# smol32src.net
KiCad netlist of a schematic drawn in EasyEDA Pro
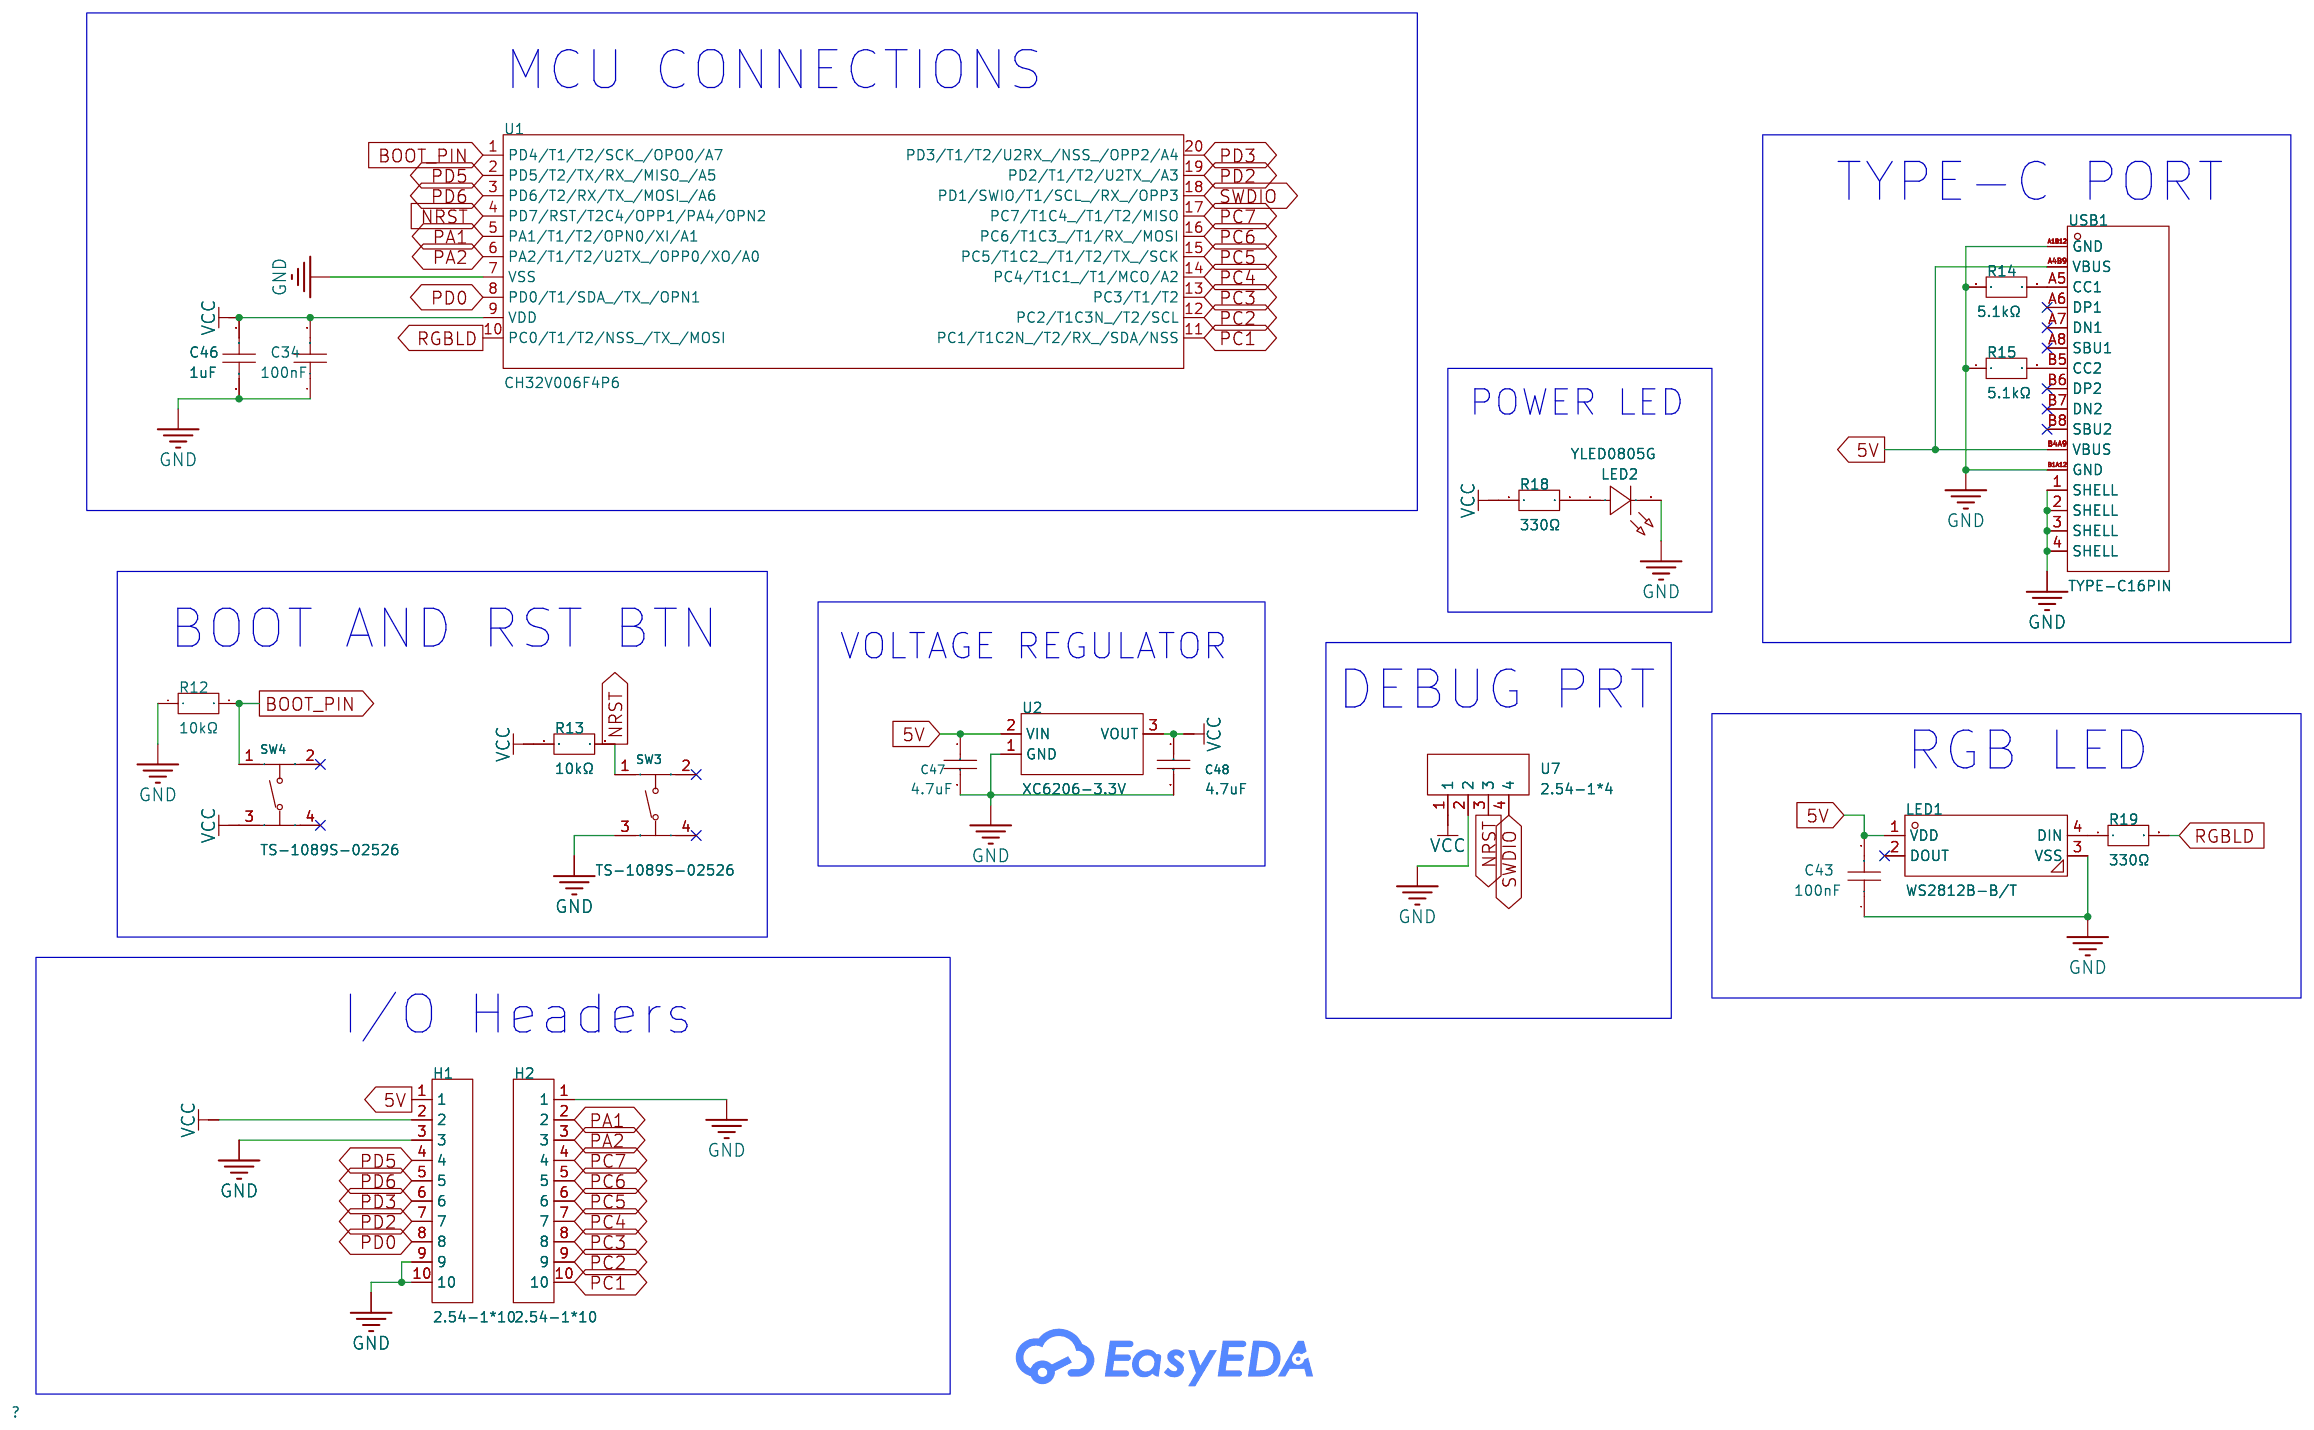
[diagram p0: schematic sheet]

(export (version "E")
  (design (tool "Eeschema 10.0.6"))
  (components
    (comp (ref "C34")
      (value "100nF")
      (footprint "easyedapro:C0603")
      (description "Capacitance:100nF Tolerance:±10% Tolerance:±10% Voltage Rating:50V Temperature Coefficient:X7R")
      (fields
        (field (name "Manufacturer Part") "FCC0603B104K500CT")
        (field (name "Manufacturer") "FOJAN(富捷)")
      )
      (libsource (lib "easyedapro") (part "FCC0603B104K500CT"))
    )
    (comp (ref "C43")
      (value "100nF")
      (footprint "easyedapro:C0603")
      (description "Capacitance:100nF Tolerance:±10% Tolerance:±10% Voltage Rating:50V Temperature Coefficient:X7R")
      (fields
        (field (name "Manufacturer Part") "FCC0603B104K500CT")
        (field (name "Manufacturer") "FOJAN(富捷)")
      )
      (libsource (lib "easyedapro") (part "FCC0603B104K500CT"))
    )
    (comp (ref "C46")
      (value "1uF")
      (footprint "easyedapro:C0603")
      (description "Capacitance:1uF Tolerance:±10% Tolerance:±10% Voltage Rating:50V Temperature Coefficient:X5R")
      (fields
        (field (name "Manufacturer Part") "CGA0603X5R105K500JT")
        (field (name "Manufacturer") "HRE(芯声)")
      )
      (libsource (lib "easyedapro") (part "CGA0603X5R105K500JT"))
    )
    (comp (ref "C47")
      (value "4.7uF")
      (footprint "easyedapro:C0603")
      (description "Capacitance:4.7uF Tolerance:±10% Tolerance:±10% Voltage Rating:10V Temperature Coefficient:X5R")
      (fields
        (field (name "Manufacturer Part") "CL10A475KP8NNNC")
        (field (name "Manufacturer") "SAMSUNG(三星)")
      )
      (libsource (lib "easyedapro") (part "CL10A475KP8NNNC"))
    )
    (comp (ref "C48")
      (value "4.7uF")
      (footprint "easyedapro:C0603")
      (description "Capacitance:4.7uF Tolerance:±10% Tolerance:±10% Voltage Rating:10V Temperature Coefficient:X5R")
      (fields
        (field (name "Manufacturer Part") "CL10A475KP8NNNC")
        (field (name "Manufacturer") "SAMSUNG(三星)")
      )
      (libsource (lib "easyedapro") (part "CL10A475KP8NNNC"))
    )
    (comp (ref "H1")
      (value "2.54-1*10")
      (footprint "easyedapro:HDR-TH_10P-P2.54-V-M")
      (fields (field (name "Manufacturer") "ZHOURI(洲日)"))
      (libsource (lib "easyedapro") (part "2.54-1*10"))
    )
    (comp (ref "H2")
      (value "2.54-1*10")
      (footprint "easyedapro:HDR-TH_10P-P2.54-V-M")
      (fields (field (name "Manufacturer") "ZHOURI(洲日)"))
      (libsource (lib "easyedapro") (part "2.54-1*10"))
    )
    (comp (ref "LED1")
      (value "WS2812B-B/T")
      (footprint "easyedapro:LED-SMD_4P-L5.0-W5.0-TL_WS2812B-B")
      (fields (field (name "Manufacturer") "worldsemi"))
      (libsource (lib "easyedapro") (part "WS2812B-B/W"))
    )
    (comp (ref "LED2")
      (value "YLED0805G")
      (footprint "easyedapro:LED0805-FD-GREEN")
      (fields (field (name "Manufacturer") "YONGYUTAI(永裕泰)"))
      (libsource (lib "easyedapro") (part "YLED0805G"))
    )
    (comp (ref "R12")
      (value "10kΩ")
      (footprint "easyedapro:R0603")
      (fields (field (name "Manufacturer Part") "FRC0603J103 TS") (field (name "Manufacturer") "FOJAN(富捷)"))
      (libsource (lib "easyedapro") (part "FRC0603J103TS"))
    )
    (comp (ref "R13")
      (value "10kΩ")
      (footprint "easyedapro:R0603")
      (fields (field (name "Manufacturer Part") "FRC0603J103 TS") (field (name "Manufacturer") "FOJAN(富捷)"))
      (libsource (lib "easyedapro") (part "FRC0603J103TS"))
    )
    (comp (ref "R14")
      (value "5.1kΩ")
      (footprint "easyedapro:R0603")
      (fields (field (name "Manufacturer Part") "FRC0603F5101TS") (field (name "Manufacturer") "FOJAN(富捷)"))
      (libsource (lib "easyedapro") (part "FRC0603F5101TS"))
    )
    (comp (ref "R15")
      (value "5.1kΩ")
      (footprint "easyedapro:R0603")
      (fields (field (name "Manufacturer Part") "FRC0603F5101TS") (field (name "Manufacturer") "FOJAN(富捷)"))
      (libsource (lib "easyedapro") (part "FRC0603F5101TS"))
    )
    (comp (ref "R18")
      (value "330Ω")
      (footprint "easyedapro:R0603")
      (fields (field (name "Manufacturer Part") "FRC0603J331 TS") (field (name "Manufacturer") "FOJAN(富捷)"))
      (libsource (lib "easyedapro") (part "FRC0603J331 TS"))
    )
    (comp (ref "R19")
      (value "330Ω")
      (footprint "easyedapro:R0603")
      (fields (field (name "Manufacturer Part") "FRC0603J331 TS") (field (name "Manufacturer") "FOJAN(富捷)"))
      (libsource (lib "easyedapro") (part "FRC0603J331 TS"))
    )
    (comp (ref "SW3")
      (value "TS-1089S-02526")
      (footprint "easyedapro:SW-SMD_4P-L4.2-W3.3-P2.15-LS5.1")
      (fields (field (name "Manufacturer") "XUNPU(讯普)"))
      (libsource (lib "easyedapro") (part "TS-1089S-02526"))
    )
    (comp (ref "SW4")
      (value "TS-1089S-02526")
      (footprint "easyedapro:SW-SMD_4P-L4.2-W3.3-P2.15-LS5.1")
      (fields (field (name "Manufacturer") "XUNPU(讯普)"))
      (libsource (lib "easyedapro") (part "TS-1089S-02526"))
    )
    (comp (ref "U1")
      (value "CH32V006F4P6")
      (footprint "easyedapro:TSSOP-20_L6.5-W4.4-P0.65-LS6.4-BL")
      (fields (field (name "Manufacturer") "WCH(南京沁恒)"))
      (libsource (lib "easyedapro") (part "CH32V006F8P6_C52753342"))
    )
    (comp (ref "U2")
      (value "XC6206-3.3V")
      (footprint "easyedapro:SOT-89-3_L4.3-W2.3-P1.50-LS4.3-BR")
      (description "Features:Short Circuit Protection；Over Current Protection")
      (fields (field (name "Manufacturer") "YONGYUTAI(永裕泰)"))
      (libsource (lib "easyedapro") (part "XC6206-3.3V_C7603199"))
    )
    (comp (ref "U7")
      (value "2.54-1*4")
      (footprint "easyedapro:HDR-TH_4P-P2.54-V-M-1")
      (fields (field (name "Manufacturer") "ZHOURI(洲日)"))
      (libsource (lib "easyedapro") (part "2.54-1*4"))
    )
    (comp (ref "USB1")
      (value "TYPE-C16PIN")
      (footprint "easyedapro:USB-C-SMD_TYPE-C16PIN")
      (fields (field (name "Manufacturer") "SHOU HAN(首韩)"))
      (libsource (lib "easyedapro") (part "TYPE-C16PIN"))
    )
  )
  (nets
    (net (code "1") (name "5V") (class "Default")
      (node (ref "C43") (pin "2") (pinfunction "2_2") (pintype "unspecified"))
      (node (ref "C47") (pin "1") (pinfunction "1_1") (pintype "input"))
      (node (ref "H1") (pin "1") (pinfunction "1_1") (pintype "unspecified"))
      (node (ref "LED1") (pin "1") (pinfunction "VDD_1") (pintype "unspecified"))
      (node (ref "U2") (pin "2") (pinfunction "VIN_2") (pintype "unspecified"))
      (node (ref "USB1") (pin "A4B9") (pinfunction "VBUS_A4B9") (pintype "unspecified"))
      (node (ref "USB1") (pin "B4A9") (pinfunction "VBUS_B4A9") (pintype "unspecified"))
    )
    (net (code "2") (name "BOOT_PIN") (class "Default")
      (node (ref "R12") (pin "2") (pinfunction "2_2") (pintype "unspecified"))
      (node (ref "SW4") (pin "1") (pinfunction "1_1") (pintype "input"))
      (node (ref "U1") (pin "1") (pinfunction "PD4/T1/T2/SCK_/OPO0/A7_1") (pintype "unspecified"))
    )
    (net (code "3") (name "GND") (class "Default")
      (node (ref "C34") (pin "1") (pinfunction "1_1") (pintype "unspecified"))
      (node (ref "C43") (pin "1") (pinfunction "1_1") (pintype "unspecified"))
      (node (ref "C46") (pin "2") (pinfunction "2_2") (pintype "unspecified"))
      (node (ref "C47") (pin "2") (pinfunction "2_2") (pintype "input"))
      (node (ref "C48") (pin "2") (pinfunction "2_2") (pintype "input"))
      (node (ref "H1") (pin "10") (pinfunction "10_10") (pintype "unspecified"))
      (node (ref "H1") (pin "3") (pinfunction "3_3") (pintype "unspecified"))
      (node (ref "H1") (pin "9") (pinfunction "9_9") (pintype "unspecified"))
      (node (ref "H2") (pin "1") (pinfunction "1_1") (pintype "unspecified"))
      (node (ref "LED1") (pin "3") (pinfunction "VSS_3") (pintype "unspecified"))
      (node (ref "LED2") (pin "2") (pinfunction "K_2") (pintype "unspecified"))
      (node (ref "R12") (pin "1") (pinfunction "1_1") (pintype "unspecified"))
      (node (ref "R14") (pin "1") (pinfunction "1_1") (pintype "unspecified"))
      (node (ref "R15") (pin "1") (pinfunction "1_1") (pintype "unspecified"))
      (node (ref "SW3") (pin "3") (pinfunction "3_3") (pintype "input"))
      (node (ref "U1") (pin "7") (pinfunction "VSS_7") (pintype "unspecified"))
      (node (ref "U2") (pin "1") (pinfunction "GND_1") (pintype "unspecified"))
      (node (ref "U7") (pin "2") (pinfunction "2_2") (pintype "unspecified"))
      (node (ref "USB1") (pin "1") (pinfunction "SHELL_1") (pintype "unspecified"))
      (node (ref "USB1") (pin "2") (pinfunction "SHELL_2") (pintype "unspecified"))
      (node (ref "USB1") (pin "3") (pinfunction "SHELL_3") (pintype "unspecified"))
      (node (ref "USB1") (pin "4") (pinfunction "SHELL_4") (pintype "unspecified"))
      (node (ref "USB1") (pin "A1B12") (pinfunction "GND_A1B12") (pintype "unspecified"))
      (node (ref "USB1") (pin "B1A12") (pinfunction "GND_B1A12") (pintype "unspecified"))
    )
    (net (code "4") (name "NRST") (class "Default")
      (node (ref "R13") (pin "2") (pinfunction "2_2") (pintype "unspecified"))
      (node (ref "SW3") (pin "1") (pinfunction "1_1") (pintype "input"))
      (node (ref "U1") (pin "4") (pinfunction "PD7/RST/T2C4/OPP1/PA4/OPN2_4") (pintype "unspecified"))
      (node (ref "U7") (pin "3") (pinfunction "3_3") (pintype "unspecified"))
    )
    (net (code "5") (name "Net-(LED1-DIN)") (class "Default")
      (node (ref "LED1") (pin "4") (pinfunction "DIN_4") (pintype "unspecified"))
      (node (ref "R19") (pin "1") (pinfunction "1_1") (pintype "unspecified"))
    )
    (net (code "6") (name "Net-(LED2-A)") (class "Default")
      (node (ref "LED2") (pin "1") (pinfunction "A_1") (pintype "unspecified"))
      (node (ref "R18") (pin "2") (pinfunction "2_2") (pintype "unspecified"))
    )
    (net (code "7") (name "Net-(USB1-CC1)") (class "Default")
      (node (ref "R14") (pin "2") (pinfunction "2_2") (pintype "unspecified"))
      (node (ref "USB1") (pin "A5") (pinfunction "CC1_A5") (pintype "unspecified"))
    )
    (net (code "8") (name "Net-(USB1-CC2)") (class "Default")
      (node (ref "R15") (pin "2") (pinfunction "2_2") (pintype "unspecified"))
      (node (ref "USB1") (pin "B5") (pinfunction "CC2_B5") (pintype "unspecified"))
    )
    (net (code "9") (name "PA1") (class "Default")
      (node (ref "H2") (pin "2") (pinfunction "2_2") (pintype "unspecified"))
      (node (ref "U1") (pin "5") (pinfunction "PA1/T1/T2/OPN0/XI/A1_5") (pintype "unspecified"))
    )
    (net (code "10") (name "PA2") (class "Default")
      (node (ref "H2") (pin "3") (pinfunction "3_3") (pintype "unspecified"))
      (node (ref "U1") (pin "6") (pinfunction "PA2/T1/T2/U2TX_/OPP0/XO/A0_6") (pintype "unspecified"))
    )
    (net (code "11") (name "PC1") (class "Default")
      (node (ref "H2") (pin "10") (pinfunction "10_10") (pintype "unspecified"))
      (node (ref "U1") (pin "11") (pinfunction "PC1/T1C2N_/T2/RX_/SDA/NSS_11") (pintype "unspecified"))
    )
    (net (code "12") (name "PC2") (class "Default")
      (node (ref "H2") (pin "9") (pinfunction "9_9") (pintype "unspecified"))
      (node (ref "U1") (pin "12") (pinfunction "PC2/T1C3N_/T2/SCL_12") (pintype "unspecified"))
    )
    (net (code "13") (name "PC3") (class "Default")
      (node (ref "H2") (pin "8") (pinfunction "8_8") (pintype "unspecified"))
      (node (ref "U1") (pin "13") (pinfunction "PC3/T1/T2_13") (pintype "unspecified"))
    )
    (net (code "14") (name "PC4") (class "Default")
      (node (ref "H2") (pin "7") (pinfunction "7_7") (pintype "unspecified"))
      (node (ref "U1") (pin "14") (pinfunction "PC4/T1C1_/T1/MCO/A2_14") (pintype "unspecified"))
    )
    (net (code "15") (name "PC5") (class "Default")
      (node (ref "H2") (pin "6") (pinfunction "6_6") (pintype "unspecified"))
      (node (ref "U1") (pin "15") (pinfunction "PC5/T1C2_/T1/T2/TX_/SCK_15") (pintype "unspecified"))
    )
    (net (code "16") (name "PC6") (class "Default")
      (node (ref "H2") (pin "5") (pinfunction "5_5") (pintype "unspecified"))
      (node (ref "U1") (pin "16") (pinfunction "PC6/T1C3_/T1/RX_/MOSI_16") (pintype "unspecified"))
    )
    (net (code "17") (name "PC7") (class "Default")
      (node (ref "H2") (pin "4") (pinfunction "4_4") (pintype "unspecified"))
      (node (ref "U1") (pin "17") (pinfunction "PC7/T1C4_/T1/T2/MISO_17") (pintype "unspecified"))
    )
    (net (code "18") (name "PD0") (class "Default")
      (node (ref "H1") (pin "8") (pinfunction "8_8") (pintype "unspecified"))
      (node (ref "U1") (pin "8") (pinfunction "PD0/T1/SDA_/TX_/OPN1_8") (pintype "unspecified"))
    )
    (net (code "19") (name "PD2") (class "Default")
      (node (ref "H1") (pin "7") (pinfunction "7_7") (pintype "unspecified"))
      (node (ref "U1") (pin "19") (pinfunction "PD2/T1/T2/U2TX_/A3_19") (pintype "unspecified"))
    )
    (net (code "20") (name "PD3") (class "Default")
      (node (ref "H1") (pin "6") (pinfunction "6_6") (pintype "unspecified"))
      (node (ref "U1") (pin "20") (pinfunction "PD3/T1/T2/U2RX_/NSS_/OPP2/A4_20") (pintype "unspecified"))
    )
    (net (code "21") (name "PD5") (class "Default")
      (node (ref "H1") (pin "4") (pinfunction "4_4") (pintype "unspecified"))
      (node (ref "U1") (pin "2") (pinfunction "PD5/T2/TX/RX_/MISO_/A5_2") (pintype "unspecified"))
    )
    (net (code "22") (name "PD6") (class "Default")
      (node (ref "H1") (pin "5") (pinfunction "5_5") (pintype "unspecified"))
      (node (ref "U1") (pin "3") (pinfunction "PD6/T2/RX/TX_/MOSI_/A6_3") (pintype "unspecified"))
    )
    (net (code "23") (name "RGBLD") (class "Default")
      (node (ref "R19") (pin "2") (pinfunction "2_2") (pintype "unspecified"))
      (node (ref "U1") (pin "10") (pinfunction "PC0/T1/T2/NSS_/TX_/MOSI_10") (pintype "unspecified"))
    )
    (net (code "24") (name "SWDIO") (class "Default")
      (node (ref "U1") (pin "18") (pinfunction "PD1/SWIO/T1/SCL_/RX_/OPP3_18") (pintype "unspecified"))
      (node (ref "U7") (pin "4") (pinfunction "4_4") (pintype "unspecified"))
    )
    (net (code "25") (name "VCC") (class "Default")
      (node (ref "C34") (pin "2") (pinfunction "2_2") (pintype "unspecified"))
      (node (ref "C46") (pin "1") (pinfunction "1_1") (pintype "unspecified"))
      (node (ref "C48") (pin "1") (pinfunction "1_1") (pintype "input"))
      (node (ref "H1") (pin "2") (pinfunction "2_2") (pintype "unspecified"))
      (node (ref "R13") (pin "1") (pinfunction "1_1") (pintype "unspecified"))
      (node (ref "R18") (pin "1") (pinfunction "1_1") (pintype "unspecified"))
      (node (ref "SW4") (pin "3") (pinfunction "3_3") (pintype "input"))
      (node (ref "U1") (pin "9") (pinfunction "VDD_9") (pintype "unspecified"))
      (node (ref "U2") (pin "3") (pinfunction "VOUT_3") (pintype "unspecified"))
      (node (ref "U7") (pin "1") (pinfunction "1_1") (pintype "unspecified"))
    )
    (net (code "26") (name "unconnected-(LED1-DOUT-Pad2)") (class "Default")
      (node (ref "LED1") (pin "2") (pinfunction "DOUT_2") (pintype "unspecified+no_connect"))
    )
    (net (code "27") (name "unconnected-(SW3-Pad2)") (class "Default")
      (node (ref "SW3") (pin "2") (pinfunction "2_2") (pintype "input+no_connect"))
    )
    (net (code "28") (name "unconnected-(SW3-Pad4)") (class "Default")
      (node (ref "SW3") (pin "4") (pinfunction "4_4") (pintype "input+no_connect"))
    )
    (net (code "29") (name "unconnected-(SW4-Pad2)") (class "Default")
      (node (ref "SW4") (pin "2") (pinfunction "2_2") (pintype "input+no_connect"))
    )
    (net (code "30") (name "unconnected-(SW4-Pad4)") (class "Default")
      (node (ref "SW4") (pin "4") (pinfunction "4_4") (pintype "input+no_connect"))
    )
    (net (code "31") (name "unconnected-(USB1-DN1-PadA7)") (class "Default")
      (node (ref "USB1") (pin "A7") (pinfunction "DN1_A7") (pintype "unspecified+no_connect"))
    )
    (net (code "32") (name "unconnected-(USB1-DN2-PadB7)") (class "Default")
      (node (ref "USB1") (pin "B7") (pinfunction "DN2_B7") (pintype "unspecified+no_connect"))
    )
    (net (code "33") (name "unconnected-(USB1-DP1-PadA6)") (class "Default")
      (node (ref "USB1") (pin "A6") (pinfunction "DP1_A6") (pintype "unspecified+no_connect"))
    )
    (net (code "34") (name "unconnected-(USB1-DP2-PadB6)") (class "Default")
      (node (ref "USB1") (pin "B6") (pinfunction "DP2_B6") (pintype "unspecified+no_connect"))
    )
    (net (code "35") (name "unconnected-(USB1-SBU1-PadA8)") (class "Default")
      (node (ref "USB1") (pin "A8") (pinfunction "SBU1_A8") (pintype "unspecified+no_connect"))
    )
    (net (code "36") (name "unconnected-(USB1-SBU2-PadB8)") (class "Default")
      (node (ref "USB1") (pin "B8") (pinfunction "SBU2_B8") (pintype "unspecified+no_connect"))
    )
  )
)
